# masterboard_b12.net
KiCad netlist of a schematic drawn in EAGLE
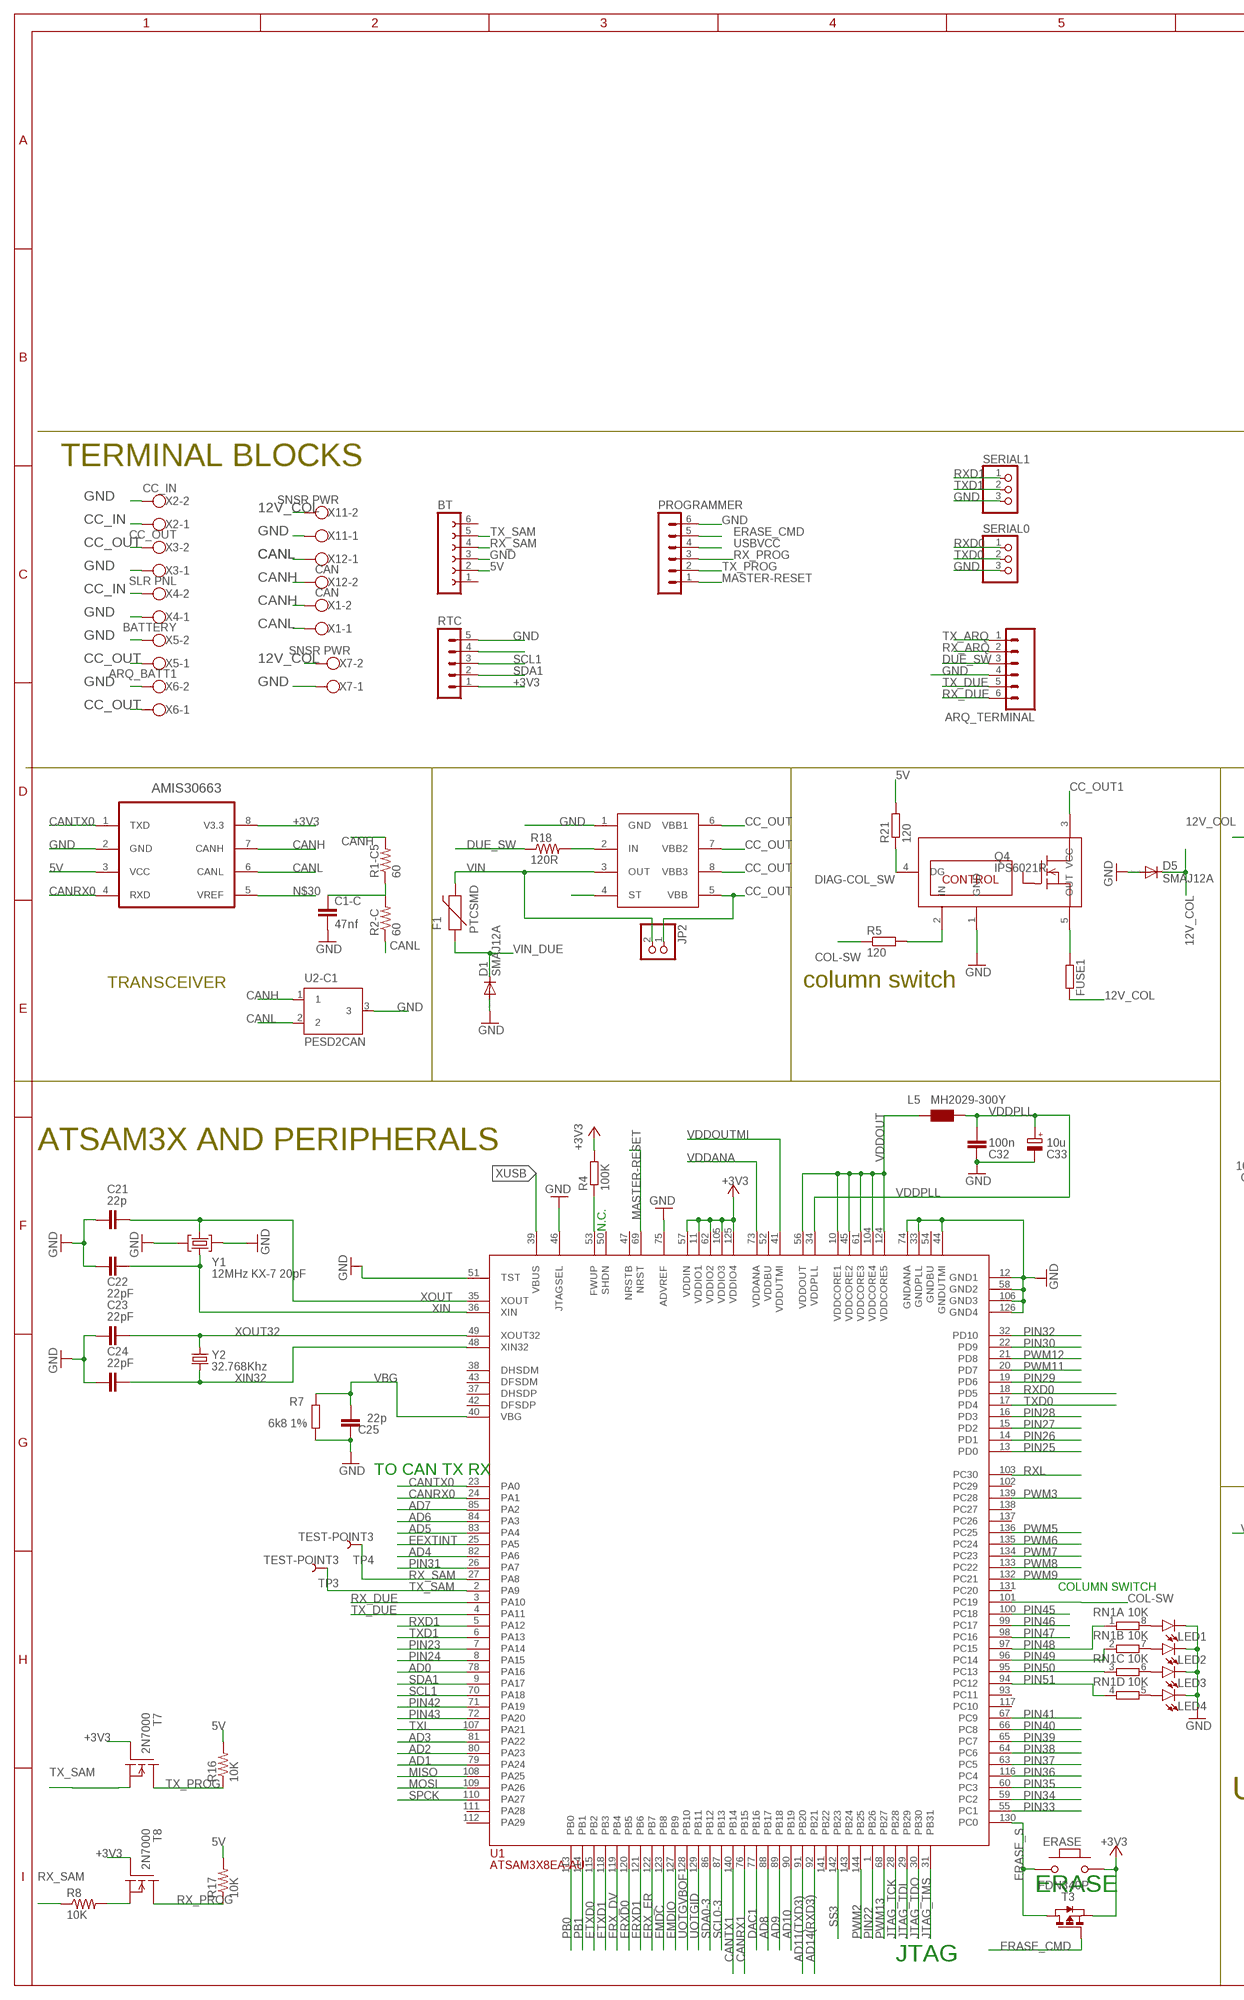
[diagram p0: schematic, sheet 1, part 1 of 2]
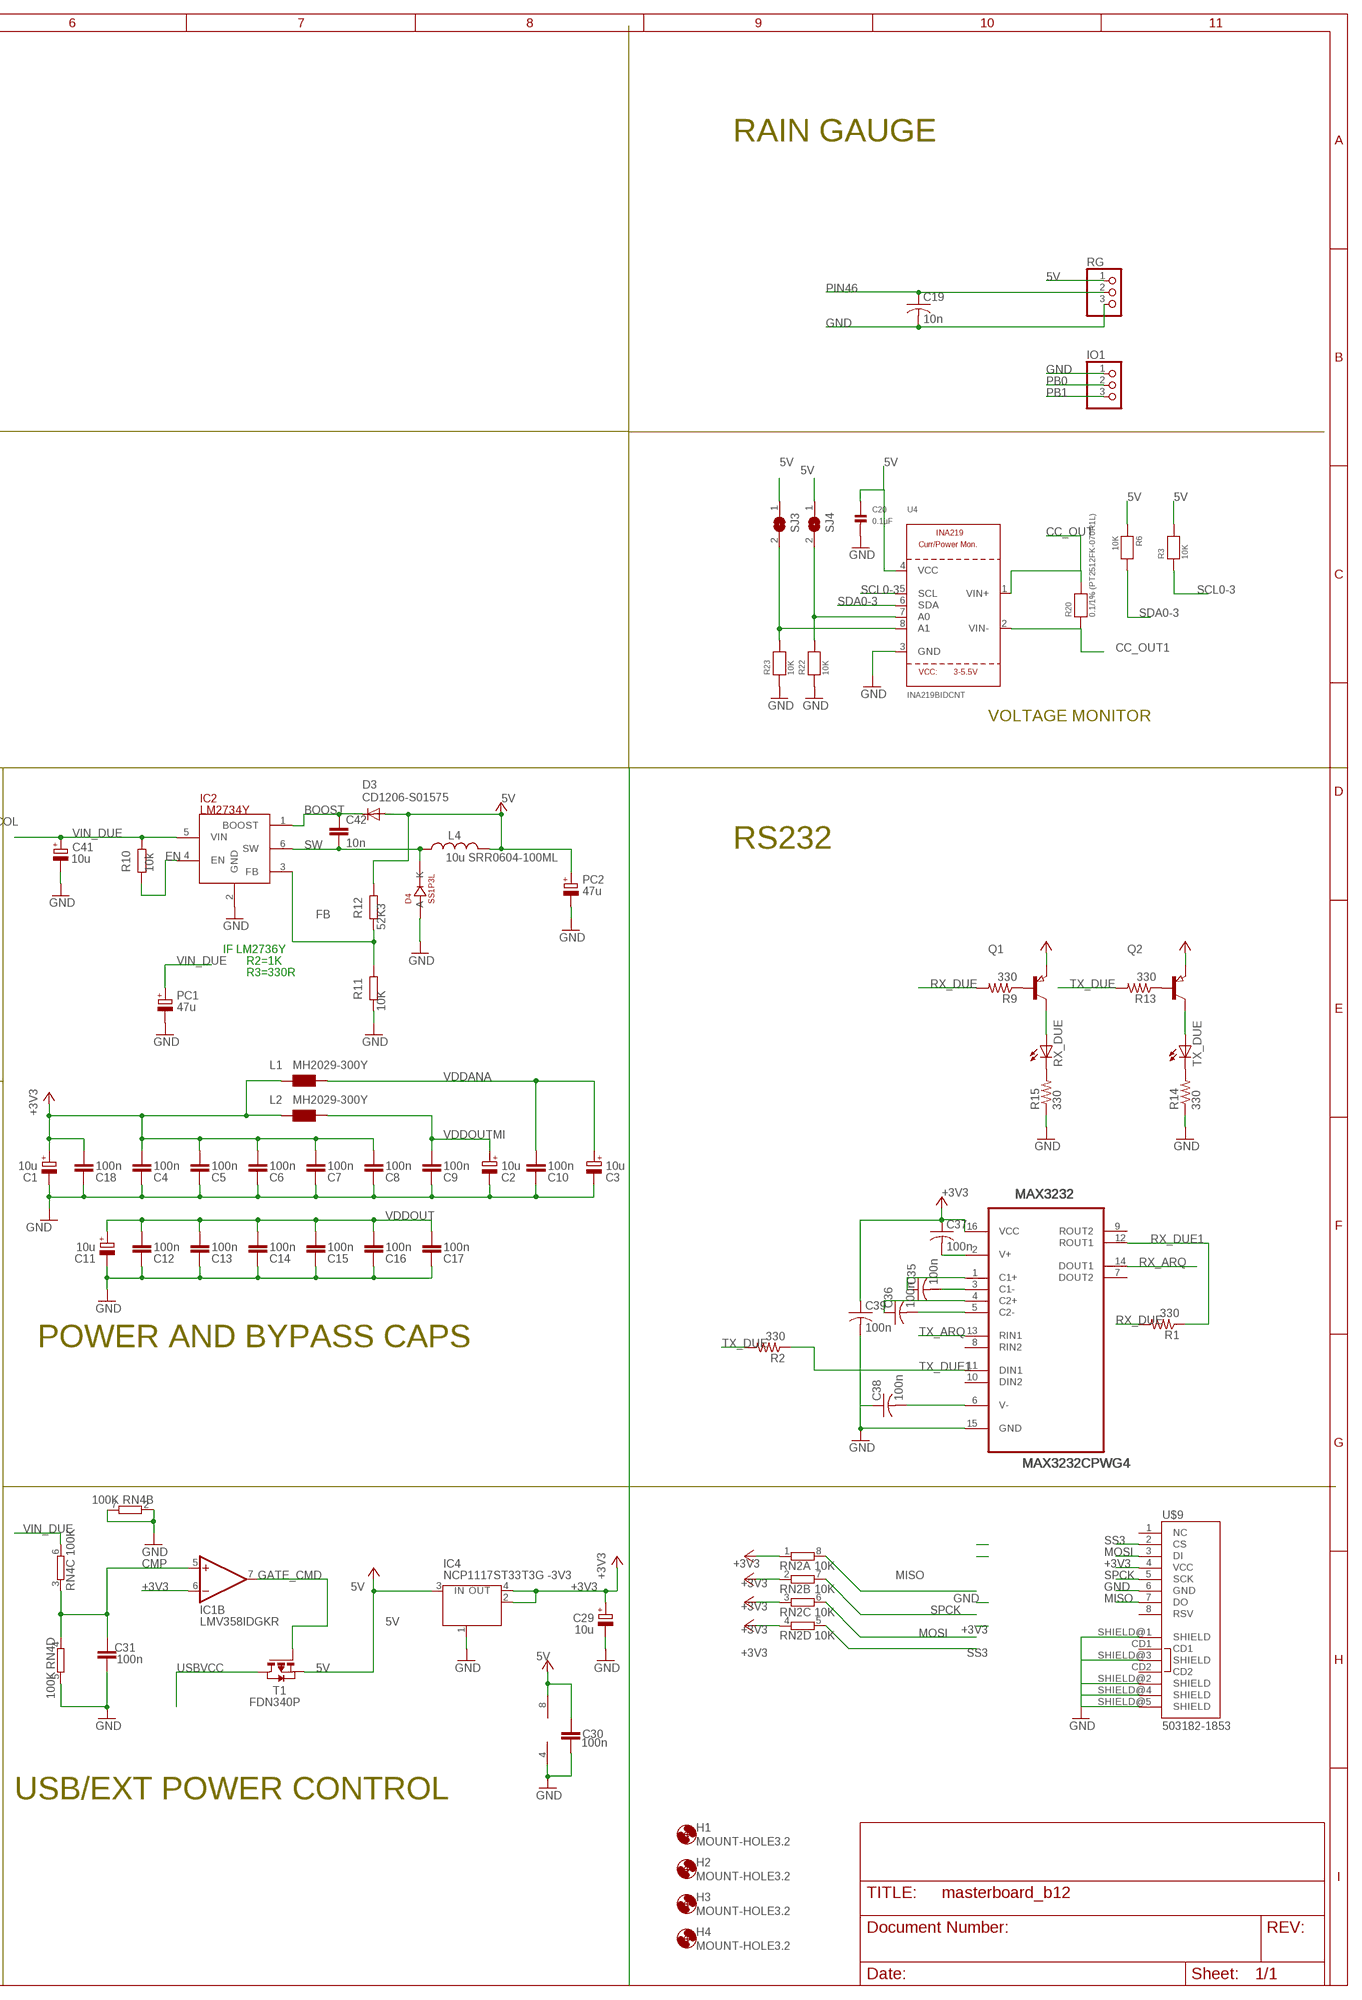
[diagram p1: schematic, sheet 1, part 2 of 2]

(export (version "E")
  (design (tool "Eeschema 10.0.6"))
  (components
    (comp (ref "ARQ_TERMINAL")
      (value "M06POLAR")
      (footprint "eagle-import:MOLEX-1X6")
      (libsource (lib "eagle-import") (part "M06POLAR"))
    )
    (comp (ref "BT")
      (value "FE06-1")
      (footprint "eagle-import:FE06")
      (libsource (lib "eagle-import") (part "FE06-1"))
    )
    (comp (ref "C1")
      (value "10u")
      (footprint "eagle-import:SMC_B")
      (libsource (lib "eagle-import") (part "CPOL-EUSMCB"))
    )
    (comp (ref "C1-C")
      (value "47nf")
      (footprint "eagle-import:C0805")
      (libsource (lib "eagle-import") (part "rcl_C-EUC0805"))
    )
    (comp (ref "C2")
      (value "10u")
      (footprint "eagle-import:SMC_B")
      (libsource (lib "eagle-import") (part "CPOL-EUSMCB"))
    )
    (comp (ref "C3")
      (value "10u")
      (footprint "eagle-import:SMC_B")
      (libsource (lib "eagle-import") (part "CPOL-EUSMCB"))
    )
    (comp (ref "C4")
      (value "100n")
      (footprint "eagle-import:C0402")
      (libsource (lib "eagle-import") (part "C-EUC0402"))
    )
    (comp (ref "C5")
      (value "100n")
      (footprint "eagle-import:C0402")
      (libsource (lib "eagle-import") (part "C-EUC0402"))
    )
    (comp (ref "C6")
      (value "100n")
      (footprint "eagle-import:C0402")
      (libsource (lib "eagle-import") (part "C-EUC0402"))
    )
    (comp (ref "C7")
      (value "100n")
      (footprint "eagle-import:C0402")
      (libsource (lib "eagle-import") (part "C-EUC0402"))
    )
    (comp (ref "C8")
      (value "100n")
      (footprint "eagle-import:C0402")
      (libsource (lib "eagle-import") (part "C-EUC0402"))
    )
    (comp (ref "C9")
      (value "100n")
      (footprint "eagle-import:C0402")
      (libsource (lib "eagle-import") (part "C-EUC0402"))
    )
    (comp (ref "C10")
      (value "100n")
      (footprint "eagle-import:C0402")
      (libsource (lib "eagle-import") (part "C-EUC0402"))
    )
    (comp (ref "C11")
      (value "10u")
      (footprint "eagle-import:SMC_B")
      (libsource (lib "eagle-import") (part "CPOL-EUSMCB"))
    )
    (comp (ref "C12")
      (value "100n")
      (footprint "eagle-import:C0402")
      (libsource (lib "eagle-import") (part "C-EUC0402"))
    )
    (comp (ref "C13")
      (value "100n")
      (footprint "eagle-import:C0402")
      (libsource (lib "eagle-import") (part "C-EUC0402"))
    )
    (comp (ref "C14")
      (value "100n")
      (footprint "eagle-import:C0402")
      (libsource (lib "eagle-import") (part "C-EUC0402"))
    )
    (comp (ref "C15")
      (value "100n")
      (footprint "eagle-import:C0402")
      (libsource (lib "eagle-import") (part "C-EUC0402"))
    )
    (comp (ref "C16")
      (value "100n")
      (footprint "eagle-import:C0402")
      (libsource (lib "eagle-import") (part "C-EUC0402"))
    )
    (comp (ref "C17")
      (value "100n")
      (footprint "eagle-import:C0402")
      (libsource (lib "eagle-import") (part "C-EUC0402"))
    )
    (comp (ref "C18")
      (value "100n")
      (footprint "eagle-import:C0402")
      (libsource (lib "eagle-import") (part "C-EUC0402"))
    )
    (comp (ref "C19")
      (value "10n")
      (footprint "eagle-import:C0603")
      (libsource (lib "eagle-import") (part "C-USC0603"))
    )
    (comp (ref "C20")
      (value "0.1µF")
      (footprint "eagle-import:0603-MINI")
      (fields (field (name "MPN") "04023C104KAT2A"))
      (libsource (lib "eagle-import") (part "CAP_CERAMIC0603MINI"))
    )
    (comp (ref "C21")
      (value "22p")
      (footprint "eagle-import:C0402")
      (libsource (lib "eagle-import") (part "C-EUC0402"))
    )
    (comp (ref "C22")
      (value "22pF")
      (footprint "eagle-import:C0402")
      (libsource (lib "eagle-import") (part "C-EUC0402"))
    )
    (comp (ref "C23")
      (value "22pF")
      (footprint "eagle-import:C0402")
      (libsource (lib "eagle-import") (part "C-EUC0402"))
    )
    (comp (ref "C24")
      (value "22pF")
      (footprint "eagle-import:C0402")
      (libsource (lib "eagle-import") (part "C-EUC0402"))
    )
    (comp (ref "C25")
      (value "22p")
      (footprint "eagle-import:C0402")
      (libsource (lib "eagle-import") (part "C-EUC0402"))
    )
    (comp (ref "C29")
      (value "10u")
      (footprint "eagle-import:SMC_B")
      (libsource (lib "eagle-import") (part "CPOL-EUSMCB"))
    )
    (comp (ref "C30")
      (value "100n")
      (footprint "eagle-import:C0402")
      (libsource (lib "eagle-import") (part "C-EUC0402"))
    )
    (comp (ref "C31")
      (value "100n")
      (footprint "eagle-import:C0402")
      (libsource (lib "eagle-import") (part "C-EUC0402"))
    )
    (comp (ref "C32")
      (value "100n")
      (footprint "eagle-import:C0402")
      (libsource (lib "eagle-import") (part "C-EUC0402"))
    )
    (comp (ref "C33")
      (value "10u")
      (footprint "eagle-import:SMC_B")
      (libsource (lib "eagle-import") (part "CPOL-EUSMCB"))
    )
    (comp (ref "C35")
      (value "100n")
      (footprint "eagle-import:C0603")
      (libsource (lib "eagle-import") (part "C-USC0603"))
    )
    (comp (ref "C36")
      (value "100n")
      (footprint "eagle-import:C0603")
      (libsource (lib "eagle-import") (part "C-USC0603"))
    )
    (comp (ref "C37")
      (value "100n")
      (footprint "eagle-import:C0603")
      (libsource (lib "eagle-import") (part "C-USC0603"))
    )
    (comp (ref "C38")
      (value "100n")
      (footprint "eagle-import:C0603")
      (libsource (lib "eagle-import") (part "C-USC0603"))
    )
    (comp (ref "C39")
      (value "100n")
      (footprint "eagle-import:C0603")
      (libsource (lib "eagle-import") (part "C-USC0603"))
    )
    (comp (ref "C41")
      (value "10u")
      (footprint "eagle-import:SMC_B")
      (libsource (lib "eagle-import") (part "CPOL-EUSMCB"))
    )
    (comp (ref "C42")
      (value "10n")
      (footprint "eagle-import:C0603-ROUND")
      (libsource (lib "eagle-import") (part "C-EUC0603"))
    )
    (comp (ref "D1")
      (value "SMAJ12A")
      (footprint "eagle-import:DO214AC")
      (libsource (lib "eagle-import") (part "DIODE-DO214AC"))
    )
    (comp (ref "D3")
      (value "CD1206-S01575")
      (footprint "eagle-import:MINIMELF")
      (libsource (lib "eagle-import") (part "DIODE-MINIMELF"))
    )
    (comp (ref "D4")
      (value "SS1P3L")
      (footprint "eagle-import:DO220AAL")
      (libsource (lib "eagle-import") (part "SS1P3L"))
    )
    (comp (ref "D5")
      (value "SMAJ12A")
      (footprint "eagle-import:DO214AC")
      (libsource (lib "eagle-import") (part "DIODE-DO214AC"))
    )
    (comp (ref "ERASE")
      (value "MYSMD_PB157")
      (footprint "eagle-import:SMD_157SW")
      (libsource (lib "eagle-import") (part "MYSMD_PB157"))
    )
    (comp (ref "F1")
      (value "PTCSMD")
      (footprint "eagle-import:PTC-1206")
      (libsource (lib "eagle-import") (part "PTCSMD"))
    )
    (comp (ref "FUSE1")
      (value "R-EU_1812X7R")
      (footprint "eagle-import:1812X7R")
      (libsource (lib "eagle-import") (part "R-EU_1812X7R"))
    )
    (comp (ref "H1")
      (value "MOUNT-HOLE3.2")
      (footprint "eagle-import:3,2")
      (libsource (lib "eagle-import") (part "MOUNT-HOLE3.2"))
    )
    (comp (ref "H2")
      (value "MOUNT-HOLE3.2")
      (footprint "eagle-import:3,2")
      (libsource (lib "eagle-import") (part "MOUNT-HOLE3.2"))
    )
    (comp (ref "H3")
      (value "MOUNT-HOLE3.2")
      (footprint "eagle-import:3,2")
      (libsource (lib "eagle-import") (part "MOUNT-HOLE3.2"))
    )
    (comp (ref "H4")
      (value "MOUNT-HOLE3.2")
      (footprint "eagle-import:3,2")
      (libsource (lib "eagle-import") (part "MOUNT-HOLE3.2"))
    )
    (comp (ref "IC1")
      (value "LMV358IDGKR")
      (footprint "eagle-import:MSOP08")
      (libsource (lib "eagle-import") (part "LMV358?MMX"))
    )
    (comp (ref "IC2")
      (value "LM2734Y")
      (footprint "eagle-import:SOT23-6")
      (libsource (lib "eagle-import") (part "LM2736Y"))
    )
    (comp (ref "IC4")
      (value "NCP1117ST33T3G -3V3")
      (footprint "eagle-import:SOT223")
      (libsource (lib "eagle-import") (part "MC33269ST-3.3T3"))
    )
    (comp (ref "IO1")
      (value "PINHD-1X3")
      (footprint "eagle-import:1X03")
      (libsource (lib "eagle-import") (part "PINHD-1X3"))
    )
    (comp (ref "JP2")
      (value "PINHD-1X2")
      (footprint "eagle-import:1X02")
      (libsource (lib "eagle-import") (part "PINHD-1X2"))
    )
    (comp (ref "L1")
      (value "MH2029-300Y")
      (footprint "eagle-import:0805")
      (libsource (lib "eagle-import") (part "WE-CBF_0805"))
    )
    (comp (ref "L2")
      (value "MH2029-300Y")
      (footprint "eagle-import:0805")
      (libsource (lib "eagle-import") (part "WE-CBF_0805"))
    )
    (comp (ref "L4")
      (value "10u SRR0604-100ML")
      (footprint "eagle-import:SRR0604")
      (libsource (lib "eagle-import") (part "L-USSRR0604"))
    )
    (comp (ref "L5")
      (value "MH2029-300Y")
      (footprint "eagle-import:0805")
      (libsource (lib "eagle-import") (part "WE-CBF_0805"))
    )
    (comp (ref "LED1")
      (value "LED0603")
      (footprint "eagle-import:LED-0603")
      (libsource (lib "eagle-import") (part "LED0603"))
    )
    (comp (ref "LED2")
      (value "LED0603")
      (footprint "eagle-import:LED-0603")
      (libsource (lib "eagle-import") (part "LED0603"))
    )
    (comp (ref "LED3")
      (value "LED0603")
      (footprint "eagle-import:LED-0603")
      (libsource (lib "eagle-import") (part "LED0603"))
    )
    (comp (ref "LED4")
      (value "LED0603")
      (footprint "eagle-import:LED-0603")
      (libsource (lib "eagle-import") (part "LED0603"))
    )
    (comp (ref "MAX3232")
      (value "MAX3232CPWG4")
      (footprint "eagle-import:SOP65P640X120-16N")
      (libsource (lib "eagle-import") (part "MAX3232CPWG4"))
    )
    (comp (ref "PC1")
      (value "47u")
      (footprint "eagle-import:PANASONIC_D")
      (libsource (lib "eagle-import") (part "CPOL-EUD"))
    )
    (comp (ref "PC2")
      (value "47u")
      (footprint "eagle-import:PANASONIC_D")
      (libsource (lib "eagle-import") (part "CPOL-EUD"))
    )
    (comp (ref "PROGRAMMER")
      (value "MA06-1")
      (footprint "eagle-import:MA06-1")
      (libsource (lib "eagle-import") (part "MA06-1"))
    )
    (comp (ref "Q1")
      (value "PNP-TRANSISTOR_SOT23")
      (footprint "eagle-import:SOT23")
      (libsource (lib "eagle-import") (part "PNP-TRANSISTOR_SOT23"))
    )
    (comp (ref "Q2")
      (value "PNP-TRANSISTOR_SOT23")
      (footprint "eagle-import:SOT23")
      (libsource (lib "eagle-import") (part "PNP-TRANSISTOR_SOT23"))
    )
    (comp (ref "Q4")
      (value "IPS6021R")
      (footprint "eagle-import:DPAK-5LEAD")
      (libsource (lib "eagle-import") (part "IPS6021R"))
    )
    (comp (ref "R1")
      (value "330")
      (footprint "eagle-import:R0603")
      (libsource (lib "eagle-import") (part "R-US_R0603"))
    )
    (comp (ref "R1-C5")
      (value "60")
      (footprint "eagle-import:R2512")
      (libsource (lib "eagle-import") (part "rcl_R-US_R2512"))
    )
    (comp (ref "R2")
      (value "330")
      (footprint "eagle-import:R0603")
      (libsource (lib "eagle-import") (part "R-US_R0603"))
    )
    (comp (ref "R2-C")
      (value "60")
      (footprint "eagle-import:R2512")
      (libsource (lib "eagle-import") (part "rcl_R-US_R2512"))
    )
    (comp (ref "R3")
      (value "10K")
      (footprint "eagle-import:0603-MINI")
      (fields (field (name "MPN") "TNPW040210K0BEED"))
      (libsource (lib "eagle-import") (part "RESISTOR0603MINI"))
    )
    (comp (ref "R4")
      (value "100K")
      (footprint "eagle-import:R0402")
      (libsource (lib "eagle-import") (part "R-EU_R0402"))
    )
    (comp (ref "R5")
      (value "120")
      (footprint "eagle-import:R0603")
      (libsource (lib "eagle-import") (part "rcl_R-EU_R0603"))
    )
    (comp (ref "R6")
      (value "10K")
      (footprint "eagle-import:0603-MINI")
      (fields (field (name "MPN") "TNPW040210K0BEED"))
      (libsource (lib "eagle-import") (part "RESISTOR0603MINI"))
    )
    (comp (ref "R7")
      (value "6k8 1%")
      (footprint "eagle-import:R0603-ROUND")
      (libsource (lib "eagle-import") (part "R-EU_R0603"))
    )
    (comp (ref "R8")
      (value "10K")
      (footprint "eagle-import:R0603")
      (libsource (lib "eagle-import") (part "rcl_R-US_R0603"))
    )
    (comp (ref "R9")
      (value "330")
      (footprint "eagle-import:R0603")
      (libsource (lib "eagle-import") (part "R-US_R0603"))
    )
    (comp (ref "R10")
      (value "10k")
      (footprint "eagle-import:R0402")
      (libsource (lib "eagle-import") (part "R-EU_R0402"))
    )
    (comp (ref "R11")
      (value "10K")
      (footprint "eagle-import:R0603-ROUND")
      (libsource (lib "eagle-import") (part "R-EU_0603-RND"))
    )
    (comp (ref "R12")
      (value "52K3")
      (footprint "eagle-import:R0603-ROUND")
      (libsource (lib "eagle-import") (part "R-EU_0603-RND"))
    )
    (comp (ref "R13")
      (value "330")
      (footprint "eagle-import:R0603")
      (libsource (lib "eagle-import") (part "R-US_R0603"))
    )
    (comp (ref "R14")
      (value "330")
      (footprint "eagle-import:R0603")
      (libsource (lib "eagle-import") (part "R-US_R0603"))
    )
    (comp (ref "R15")
      (value "330")
      (footprint "eagle-import:R0603")
      (libsource (lib "eagle-import") (part "R-US_R0603"))
    )
    (comp (ref "R16")
      (value "10K")
      (footprint "eagle-import:R0603")
      (libsource (lib "eagle-import") (part "rcl_R-US_R0603"))
    )
    (comp (ref "R17")
      (value "10K")
      (footprint "eagle-import:R0603")
      (libsource (lib "eagle-import") (part "rcl_R-US_R0603"))
    )
    (comp (ref "R18")
      (value "120R")
      (footprint "eagle-import:R0603")
      (libsource (lib "eagle-import") (part "rcl_R-US_R0603"))
    )
    (comp (ref "R20")
      (value "0.1/1% (PT2512FK-070R1L)")
      (footprint "eagle-import:2512")
      (libsource (lib "eagle-import") (part "RESISTOR2512"))
    )
    (comp (ref "R21")
      (value "120")
      (footprint "eagle-import:R0603")
      (libsource (lib "eagle-import") (part "rcl_R-EU_R0603"))
    )
    (comp (ref "R22")
      (value "10K")
      (footprint "eagle-import:0603-MINI")
      (fields (field (name "MPN") "TNPW040210K0BEED"))
      (libsource (lib "eagle-import") (part "RESISTOR0603MINI"))
    )
    (comp (ref "R23")
      (value "10K")
      (footprint "eagle-import:0603-MINI")
      (fields (field (name "MPN") "TNPW040210K0BEED"))
      (libsource (lib "eagle-import") (part "RESISTOR0603MINI"))
    )
    (comp (ref "RG")
      (value "PINHD-1X3")
      (footprint "eagle-import:1X03")
      (libsource (lib "eagle-import") (part "PINHD-1X3"))
    )
    (comp (ref "RN1")
      (value "10K")
      (footprint "eagle-import:CAT16")
      (libsource (lib "eagle-import") (part "4R-NCAT16"))
    )
    (comp (ref "RN2")
      (value "10K")
      (footprint "eagle-import:CAT16")
      (libsource (lib "eagle-import") (part "4R-NCAT16"))
    )
    (comp (ref "RN4")
      (value "100K")
      (footprint "eagle-import:CAT16")
      (libsource (lib "eagle-import") (part "4R-NCAT16"))
    )
    (comp (ref "RTC")
      (value "MA05-1")
      (footprint "eagle-import:MA05-1")
      (libsource (lib "eagle-import") (part "MA05-1"))
    )
    (comp (ref "RX_DUE")
      (value "LEDCHIPLED_0603")
      (footprint "eagle-import:CHIPLED_0603")
      (libsource (lib "eagle-import") (part "LEDCHIPLED_0603"))
    )
    (comp (ref "SERIAL0")
      (value "PINHD-1X3")
      (footprint "eagle-import:1X03")
      (libsource (lib "eagle-import") (part "PINHD-1X3"))
    )
    (comp (ref "SERIAL1")
      (value "PINHD-1X3")
      (footprint "eagle-import:1X03")
      (libsource (lib "eagle-import") (part "PINHD-1X3"))
    )
    (comp (ref "SJ3")
      (value "SOLDERJUMPERREFLOW_NOPASTE")
      (footprint "eagle-import:SOLDERJUMPER_REFLOW_NOPASTE")
      (libsource (lib "eagle-import") (part "SOLDERJUMPERREFLOW_NOPASTE"))
    )
    (comp (ref "SJ4")
      (value "SOLDERJUMPERREFLOW_NOPASTE")
      (footprint "eagle-import:SOLDERJUMPER_REFLOW_NOPASTE")
      (libsource (lib "eagle-import") (part "SOLDERJUMPERREFLOW_NOPASTE"))
    )
    (comp (ref "T1")
      (value "FDN340P")
      (footprint "eagle-import:SOT-23")
      (libsource (lib "eagle-import") (part "PMOSSOT23"))
    )
    (comp (ref "T3")
      (value "FDN340P")
      (footprint "eagle-import:SOT-23")
      (libsource (lib "eagle-import") (part "PMOSSOT23"))
    )
    (comp (ref "T7")
      (value "2N7000")
      (footprint "eagle-import:SOT23")
      (libsource (lib "eagle-import") (part "2N7000"))
    )
    (comp (ref "T8")
      (value "2N7000")
      (footprint "eagle-import:SOT23")
      (libsource (lib "eagle-import") (part "2N7000"))
    )
    (comp (ref "TP3")
      (value "TEST-POINT3")
      (footprint "eagle-import:PAD.03X.03")
      (libsource (lib "eagle-import") (part "TEST-POINT3"))
    )
    (comp (ref "TP4")
      (value "TEST-POINT3")
      (footprint "eagle-import:PAD.03X.03")
      (libsource (lib "eagle-import") (part "TEST-POINT3"))
    )
    (comp (ref "TX_DUE")
      (value "LEDCHIPLED_0603")
      (footprint "eagle-import:CHIPLED_0603")
      (libsource (lib "eagle-import") (part "LEDCHIPLED_0603"))
    )
    (comp (ref "U$9")
      (value "503182-1853")
      (footprint "eagle-import:503182-1853")
      (libsource (lib "eagle-import") (part "503182-1853"))
    )
    (comp (ref "U1")
      (value "ATSAM3X8EA-AU")
      (footprint "eagle-import:LQFP144")
      (libsource (lib "eagle-import") (part "ATSAM3X/AAU"))
    )
    (comp (ref "U2")
      (value "INF-PG-DSO-8-24_L_1")
      (footprint "eagle-import:INF-PG-DSO-8-24_L_1PRIMARY")
      (libsource (lib "eagle-import") (part "INF-PG-DSO-8-24_L_1"))
    )
    (comp (ref "U2-C")
      (value "AMIS30663CAN")
      (footprint "eagle-import:SOIC8")
      (fields (field (name "MPN") "AMIS30663"))
      (libsource (lib "eagle-import") (part "AMIS30663CAN"))
    )
    (comp (ref "U2-C1")
      (value "PESD2CAN")
      (footprint "eagle-import:SOT23")
      (libsource (lib "eagle-import") (part "PESD2CAN"))
    )
    (comp (ref "U4")
      (value "INA219BIDCNT")
      (footprint "eagle-import:SOT23-8")
      (libsource (lib "eagle-import") (part "INA219"))
    )
    (comp (ref "X1")
      (value "CAN")
      (footprint "eagle-import:W237-102")
      (fields (field (name "MPN") "237-102"))
      (libsource (lib "eagle-import") (part "W237-102"))
    )
    (comp (ref "X2")
      (value "CC_IN")
      (footprint "eagle-import:W237-102")
      (fields (field (name "MPN") "237-102"))
      (libsource (lib "eagle-import") (part "W237-102"))
    )
    (comp (ref "X3")
      (value "CC_OUT")
      (footprint "eagle-import:W237-102")
      (fields (field (name "MPN") "237-102"))
      (libsource (lib "eagle-import") (part "W237-102"))
    )
    (comp (ref "X4")
      (value "SLR PNL")
      (footprint "eagle-import:W237-102")
      (fields (field (name "MPN") "237-102"))
      (libsource (lib "eagle-import") (part "W237-102"))
    )
    (comp (ref "X5")
      (value "BATTERY")
      (footprint "eagle-import:W237-102")
      (fields (field (name "MPN") "237-102"))
      (libsource (lib "eagle-import") (part "W237-102"))
    )
    (comp (ref "X6")
      (value "ARQ_BATT1")
      (footprint "eagle-import:W237-102")
      (fields (field (name "MPN") "237-102"))
      (libsource (lib "eagle-import") (part "W237-102"))
    )
    (comp (ref "X7")
      (value "SNSR PWR")
      (footprint "eagle-import:W237-102")
      (fields (field (name "MPN") "237-102"))
      (libsource (lib "eagle-import") (part "W237-102"))
    )
    (comp (ref "X11")
      (value "SNSR PWR")
      (footprint "eagle-import:W237-102")
      (fields (field (name "MPN") "237-102"))
      (libsource (lib "eagle-import") (part "W237-102"))
    )
    (comp (ref "X12")
      (value "CAN")
      (footprint "eagle-import:W237-102")
      (fields (field (name "MPN") "237-102"))
      (libsource (lib "eagle-import") (part "W237-102"))
    )
    (comp (ref "Y1")
      (value "12MHz KX-7 20pF")
      (footprint "eagle-import:CRYSTAL-3.2-2.5")
      (libsource (lib "eagle-import") (part "CRYSTAL-3.2-2.5"))
    )
    (comp (ref "Y2")
      (value "32.768Khz")
      (footprint "eagle-import:RESONATOR_EPSON_FC_145")
      (libsource (lib "eagle-import") (part "RESONATOR_EPSON_FC_145"))
    )
  )
  (nets
    (net (code "1") (name "+3V3") (class "Default")
      (node (ref "C1") (pin "+") (pinfunction "+_+") (pintype "passive"))
      (node (ref "C18") (pin "2") (pinfunction "2_2") (pintype "passive"))
      (node (ref "C29") (pin "+") (pinfunction "+_+") (pintype "passive"))
      (node (ref "C37") (pin "1") (pinfunction "1_1") (pintype "passive"))
      (node (ref "C39") (pin "1") (pinfunction "1_1") (pintype "passive"))
      (node (ref "C4") (pin "2") (pinfunction "2_2") (pintype "passive"))
      (node (ref "C5") (pin "2") (pinfunction "2_2") (pintype "passive"))
      (node (ref "C6") (pin "2") (pinfunction "2_2") (pintype "passive"))
      (node (ref "C7") (pin "2") (pinfunction "2_2") (pintype "passive"))
      (node (ref "C8") (pin "2") (pinfunction "2_2") (pintype "passive"))
      (node (ref "ERASE") (pin "1") (pinfunction "1_1") (pintype "passive"))
      (node (ref "IC1") (pin "6") (pinfunction "-IN_6") (pintype "input"))
      (node (ref "IC4") (pin "2") (pinfunction "OUT_2") (pintype "passive"))
      (node (ref "IC4") (pin "4") (pinfunction "OUT_4") (pintype "passive"))
      (node (ref "L1") (pin "1") (pinfunction "1_1") (pintype "passive"))
      (node (ref "L2") (pin "1") (pinfunction "1_1") (pintype "passive"))
      (node (ref "MAX3232") (pin "16") (pinfunction "VCC_16") (pintype "power_in"))
      (node (ref "Q1") (pin "2") (pinfunction "E_2") (pintype "passive"))
      (node (ref "Q2") (pin "2") (pinfunction "E_2") (pintype "passive"))
      (node (ref "R4") (pin "2") (pinfunction "2_2") (pintype "passive"))
      (node (ref "RN2") (pin "1") (pinfunction "1_1") (pintype "passive"))
      (node (ref "RN2") (pin "2") (pinfunction "1_2") (pintype "passive"))
      (node (ref "RN2") (pin "3") (pinfunction "1_3") (pintype "passive"))
      (node (ref "RN2") (pin "4") (pinfunction "1_4") (pintype "passive"))
      (node (ref "RTC") (pin "1") (pinfunction "1_1") (pintype "passive"))
      (node (ref "T3") (pin "2") (pinfunction "S_2") (pintype "passive"))
      (node (ref "T7") (pin "1") (pinfunction "G_1") (pintype "passive"))
      (node (ref "T8") (pin "1") (pinfunction "G_1") (pintype "passive"))
      (node (ref "U$9") (pin "4") (pinfunction "VCC_4") (pintype "bidirectional"))
      (node (ref "U1") (pin "105") (pinfunction "VDDIO3_105") (pintype "power_in"))
      (node (ref "U1") (pin "11") (pinfunction "VDDIO1_11") (pintype "power_in"))
      (node (ref "U1") (pin "125") (pinfunction "VDDIO4_125") (pintype "power_in"))
      (node (ref "U1") (pin "57") (pinfunction "VDDIN_57") (pintype "power_in"))
      (node (ref "U1") (pin "62") (pinfunction "VDDIO2_62") (pintype "power_in"))
      (node (ref "U2-C") (pin "8") (pinfunction "V3.3_8") (pintype "bidirectional"))
    )
    (net (code "2") (name "+5V") (class "Default")
      (node (ref "BT") (pin "2") (pinfunction "2_2") (pintype "passive"))
      (node (ref "C20") (pin "1") (pinfunction "P$1_1") (pintype "passive"))
      (node (ref "C30") (pin "2") (pinfunction "2_2") (pintype "passive"))
      (node (ref "D3") (pin "A") (pinfunction "A_A") (pintype "passive"))
      (node (ref "IC1") (pin "8") (pinfunction "V+_8") (pintype "power_in"))
      (node (ref "IC4") (pin "3") (pinfunction "IN_3") (pintype "input"))
      (node (ref "L4") (pin "P$2") (pinfunction "2_P$2") (pintype "passive"))
      (node (ref "PC2") (pin "+") (pinfunction "+_+") (pintype "passive"))
      (node (ref "R12") (pin "1") (pinfunction "1_1") (pintype "passive"))
      (node (ref "R16") (pin "2") (pinfunction "2_2") (pintype "passive"))
      (node (ref "R17") (pin "2") (pinfunction "2_2") (pintype "passive"))
      (node (ref "R21") (pin "2") (pinfunction "2_2") (pintype "passive"))
      (node (ref "R3") (pin "2") (pinfunction "2_2") (pintype "passive"))
      (node (ref "R6") (pin "1") (pinfunction "1_1") (pintype "passive"))
      (node (ref "RG") (pin "1") (pinfunction "1_1") (pintype "passive"))
      (node (ref "SJ3") (pin "1") (pinfunction "1_1") (pintype "passive"))
      (node (ref "SJ4") (pin "1") (pinfunction "1_1") (pintype "passive"))
      (node (ref "T1") (pin "2") (pinfunction "S_2") (pintype "passive"))
      (node (ref "U2-C") (pin "3") (pinfunction "VCC_3") (pintype "bidirectional"))
      (node (ref "U4") (pin "4") (pinfunction "VCC_4") (pintype "bidirectional"))
    )
    (net (code "3") (name "/12V_COL") (class "Default")
      (node (ref "D5") (pin "C") (pinfunction "C_C") (pintype "passive"))
      (node (ref "FUSE1") (pin "2") (pinfunction "2_2") (pintype "passive"))
      (node (ref "X11") (pin "2") (pinfunction "KL_2") (pintype "passive"))
      (node (ref "X7") (pin "2") (pinfunction "KL_2") (pintype "passive"))
    )
    (net (code "4") (name "/AD0") (class "Default")
      (node (ref "U1") (pin "78") (pinfunction "PA16_78") (pintype "bidirectional"))
    )
    (net (code "5") (name "/AD1") (class "Default")
      (node (ref "U1") (pin "79") (pinfunction "PA24_79") (pintype "bidirectional"))
    )
    (net (code "6") (name "/AD2") (class "Default")
      (node (ref "U1") (pin "80") (pinfunction "PA23_80") (pintype "bidirectional"))
    )
    (net (code "7") (name "/AD3") (class "Default")
      (node (ref "U1") (pin "81") (pinfunction "PA22_81") (pintype "bidirectional"))
    )
    (net (code "8") (name "/AD4") (class "Default")
      (node (ref "U1") (pin "82") (pinfunction "PA6_82") (pintype "bidirectional"))
    )
    (net (code "9") (name "/AD5") (class "Default")
      (node (ref "U1") (pin "83") (pinfunction "PA4_83") (pintype "bidirectional"))
    )
    (net (code "10") (name "/AD6") (class "Default")
      (node (ref "U1") (pin "84") (pinfunction "PA3_84") (pintype "bidirectional"))
    )
    (net (code "11") (name "/AD7") (class "Default")
      (node (ref "U1") (pin "85") (pinfunction "PA2_85") (pintype "bidirectional"))
    )
    (net (code "12") (name "/AD8") (class "Default")
      (node (ref "U1") (pin "88") (pinfunction "PB17_88") (pintype "bidirectional"))
    )
    (net (code "13") (name "/AD9") (class "Default")
      (node (ref "U1") (pin "89") (pinfunction "PB18_89") (pintype "bidirectional"))
    )
    (net (code "14") (name "/AD10") (class "Default")
      (node (ref "U1") (pin "90") (pinfunction "PB19_90") (pintype "bidirectional"))
    )
    (net (code "15") (name "/AD11(TXD3)") (class "Default")
      (node (ref "U1") (pin "91") (pinfunction "PB20_91") (pintype "bidirectional"))
    )
    (net (code "16") (name "/AD14(RXD3)") (class "Default")
      (node (ref "U1") (pin "92") (pinfunction "PB21_92") (pintype "bidirectional"))
    )
    (net (code "17") (name "/BOOST") (class "Default")
      (node (ref "C42") (pin "1") (pinfunction "1_1") (pintype "passive"))
      (node (ref "D3") (pin "C") (pinfunction "C_C") (pintype "passive"))
      (node (ref "IC2") (pin "1") (pinfunction "BOOST_1") (pintype "input"))
    )
    (net (code "18") (name "/CANH") (class "Default")
      (node (ref "R1-C5") (pin "2") (pinfunction "2_2") (pintype "passive"))
      (node (ref "U2-C") (pin "7") (pinfunction "CANH_7") (pintype "bidirectional"))
      (node (ref "U2-C1") (pin "1") (pinfunction "1_1") (pintype "input"))
      (node (ref "X1") (pin "2") (pinfunction "KL_2") (pintype "passive"))
      (node (ref "X12") (pin "2") (pinfunction "KL_2") (pintype "passive"))
    )
    (net (code "19") (name "/CANL") (class "Default")
      (node (ref "R2-C") (pin "1") (pinfunction "1_1") (pintype "passive"))
      (node (ref "U2-C") (pin "6") (pinfunction "CANL_6") (pintype "bidirectional"))
      (node (ref "U2-C1") (pin "2") (pinfunction "2_2") (pintype "power_in"))
      (node (ref "X1") (pin "1") (pinfunction "KL_1") (pintype "passive"))
      (node (ref "X12") (pin "1") (pinfunction "KL_1") (pintype "passive"))
    )
    (net (code "20") (name "/CANRX0") (class "Default")
      (node (ref "U1") (pin "24") (pinfunction "PA1_24") (pintype "bidirectional"))
      (node (ref "U2-C") (pin "4") (pinfunction "RXD_4") (pintype "bidirectional"))
    )
    (net (code "21") (name "/CANRX1") (class "Default")
      (node (ref "U1") (pin "76") (pinfunction "PB15_76") (pintype "bidirectional"))
    )
    (net (code "22") (name "/CANTX0") (class "Default")
      (node (ref "U1") (pin "23") (pinfunction "PA0_23") (pintype "bidirectional"))
      (node (ref "U2-C") (pin "1") (pinfunction "TXD_1") (pintype "bidirectional"))
    )
    (net (code "23") (name "/CANTX1") (class "Default")
      (node (ref "U1") (pin "140") (pinfunction "PB14_140") (pintype "bidirectional"))
    )
    (net (code "24") (name "/CC_IN") (class "Default")
      (node (ref "X2") (pin "1") (pinfunction "KL_1") (pintype "passive"))
      (node (ref "X4") (pin "2") (pinfunction "KL_2") (pintype "passive"))
    )
    (net (code "25") (name "/CC_OUT") (class "Default")
      (node (ref "JP2") (pin "1") (pinfunction "1_1") (pintype "passive"))
      (node (ref "R20") (pin "2") (pinfunction "2_2") (pintype "passive"))
      (node (ref "U2") (pin "5") (pinfunction "VBB_5") (pintype "bidirectional"))
      (node (ref "U2") (pin "6") (pinfunction "VBB1_6") (pintype "bidirectional"))
      (node (ref "U2") (pin "7") (pinfunction "VBB2_7") (pintype "bidirectional"))
      (node (ref "U2") (pin "8") (pinfunction "VBB3_8") (pintype "bidirectional"))
      (node (ref "U4") (pin "1") (pinfunction "VIN+_1") (pintype "bidirectional"))
      (node (ref "X3") (pin "2") (pinfunction "KL_2") (pintype "passive"))
      (node (ref "X5") (pin "1") (pinfunction "KL_1") (pintype "passive"))
      (node (ref "X6") (pin "1") (pinfunction "KL_1") (pintype "passive"))
    )
    (net (code "26") (name "/CC_OUT1") (class "Default")
      (node (ref "Q4") (pin "3") (pinfunction "VCC_3") (pintype "passive"))
      (node (ref "R20") (pin "1") (pinfunction "1_1") (pintype "passive"))
      (node (ref "U4") (pin "2") (pinfunction "VIN-_2") (pintype "bidirectional"))
    )
    (net (code "27") (name "/CMP") (class "Default")
      (node (ref "C31") (pin "2") (pinfunction "2_2") (pintype "passive"))
      (node (ref "IC1") (pin "5") (pinfunction "+IN_5") (pintype "input"))
      (node (ref "RN4") (pin "3") (pinfunction "1_3") (pintype "passive"))
      (node (ref "RN4") (pin "4") (pinfunction "1_4") (pintype "passive"))
    )
    (net (code "28") (name "/COL-SW") (class "Default")
      (node (ref "R5") (pin "1") (pinfunction "1_1") (pintype "passive"))
      (node (ref "U1") (pin "101") (pinfunction "PC19_101") (pintype "bidirectional"))
    )
    (net (code "29") (name "/DAC1") (class "Default")
      (node (ref "U1") (pin "77") (pinfunction "PB16_77") (pintype "bidirectional"))
    )
    (net (code "30") (name "/DIAG-COL_SW") (class "Default")
      (node (ref "Q4") (pin "4") (pinfunction "DG_4") (pintype "passive"))
      (node (ref "R21") (pin "1") (pinfunction "1_1") (pintype "passive"))
    )
    (net (code "31") (name "/DUE_SW") (class "Default")
      (node (ref "ARQ_TERMINAL") (pin "3") (pinfunction "3_3") (pintype "passive"))
      (node (ref "R18") (pin "1") (pinfunction "1_1") (pintype "passive"))
    )
    (net (code "32") (name "/EEXTINT") (class "Default")
      (node (ref "U1") (pin "25") (pinfunction "PA5_25") (pintype "bidirectional"))
    )
    (net (code "33") (name "/EMDC") (class "Default")
      (node (ref "U1") (pin "123") (pinfunction "PB8_123") (pintype "bidirectional"))
    )
    (net (code "34") (name "/EMDIO") (class "Default")
      (node (ref "U1") (pin "127") (pinfunction "PB9_127") (pintype "bidirectional"))
    )
    (net (code "35") (name "/EN") (class "Default")
      (node (ref "IC2") (pin "4") (pinfunction "EN_4") (pintype "input"))
      (node (ref "R10") (pin "2") (pinfunction "2_2") (pintype "passive"))
    )
    (net (code "36") (name "/ERASE_CMD") (class "Default")
      (node (ref "PROGRAMMER") (pin "5") (pinfunction "5_5") (pintype "passive"))
      (node (ref "T3") (pin "3") (pinfunction "G_3") (pintype "passive"))
    )
    (net (code "37") (name "/ERASE_S") (class "Default")
      (node (ref "ERASE") (pin "2") (pinfunction "2_2") (pintype "passive"))
      (node (ref "T3") (pin "1") (pinfunction "D_1") (pintype "passive"))
      (node (ref "U1") (pin "130") (pinfunction "PC0_130") (pintype "bidirectional"))
    )
    (net (code "38") (name "/ERXD0") (class "Default")
      (node (ref "U1") (pin "120") (pinfunction "PB5_120") (pintype "bidirectional"))
    )
    (net (code "39") (name "/ERXD1") (class "Default")
      (node (ref "U1") (pin "121") (pinfunction "PB6_121") (pintype "bidirectional"))
    )
    (net (code "40") (name "/ERX_DV") (class "Default")
      (node (ref "U1") (pin "119") (pinfunction "PB4_119") (pintype "bidirectional"))
    )
    (net (code "41") (name "/ERX_ER") (class "Default")
      (node (ref "U1") (pin "122") (pinfunction "PB7_122") (pintype "bidirectional"))
    )
    (net (code "42") (name "/ETXD0") (class "Default")
      (node (ref "U1") (pin "115") (pinfunction "PB2_115") (pintype "bidirectional"))
    )
    (net (code "43") (name "/ETXD1") (class "Default")
      (node (ref "U1") (pin "118") (pinfunction "PB3_118") (pintype "bidirectional"))
    )
    (net (code "44") (name "/FB") (class "Default")
      (node (ref "IC2") (pin "3") (pinfunction "FB_3") (pintype "input"))
      (node (ref "R11") (pin "1") (pinfunction "1_1") (pintype "passive"))
      (node (ref "R12") (pin "2") (pinfunction "2_2") (pintype "passive"))
    )
    (net (code "45") (name "/GATE_CMD") (class "Default")
      (node (ref "IC1") (pin "7") (pinfunction "OUT_7") (pintype "output"))
      (node (ref "T1") (pin "3") (pinfunction "G_3") (pintype "passive"))
    )
    (net (code "46") (name "/GNDBU") (class "Default")
      (node (ref "U1") (pin "54") (pinfunction "GNDBU_54") (pintype "power_in"))
    )
    (net (code "47") (name "/JTAG_TCK") (class "Default")
      (node (ref "U1") (pin "28") (pinfunction "PB28_28") (pintype "bidirectional"))
    )
    (net (code "48") (name "/JTAG_TDI") (class "Default")
      (node (ref "U1") (pin "29") (pinfunction "PB29_29") (pintype "bidirectional"))
    )
    (net (code "49") (name "/JTAG_TDO") (class "Default")
      (node (ref "U1") (pin "30") (pinfunction "PB30_30") (pintype "bidirectional"))
    )
    (net (code "50") (name "/JTAG_TMS") (class "Default")
      (node (ref "U1") (pin "31") (pinfunction "PB31_31") (pintype "bidirectional"))
    )
    (net (code "51") (name "/MASTER-RESET") (class "Default")
      (node (ref "PROGRAMMER") (pin "1") (pinfunction "1_1") (pintype "passive"))
      (node (ref "U1") (pin "69") (pinfunction "NRST_69") (pintype "bidirectional"))
    )
    (net (code "52") (name "/MISO") (class "Default")
      (node (ref "RN2") (pin "8") (pinfunction "2_8") (pintype "passive"))
      (node (ref "U$9") (pin "7") (pinfunction "DO_7") (pintype "bidirectional"))
      (node (ref "U1") (pin "108") (pinfunction "PA25_108") (pintype "bidirectional"))
    )
    (net (code "53") (name "/MOSI") (class "Default")
      (node (ref "RN2") (pin "6") (pinfunction "2_6") (pintype "passive"))
      (node (ref "U$9") (pin "3") (pinfunction "DI_3") (pintype "bidirectional"))
      (node (ref "U1") (pin "109") (pinfunction "PA26_109") (pintype "bidirectional"))
    )
    (net (code "54") (name "/N$30") (class "Default")
      (node (ref "U2-C") (pin "5") (pinfunction "VREF_5") (pintype "bidirectional"))
    )
    (net (code "55") (name "/PB0") (class "Default")
      (node (ref "IO1") (pin "2") (pinfunction "2_2") (pintype "passive"))
      (node (ref "U1") (pin "113") (pinfunction "PB0_113") (pintype "bidirectional"))
    )
    (net (code "56") (name "/PB1") (class "Default")
      (node (ref "IO1") (pin "3") (pinfunction "3_3") (pintype "passive"))
      (node (ref "U1") (pin "114") (pinfunction "PB1_114") (pintype "bidirectional"))
    )
    (net (code "57") (name "/PIN22") (class "Default")
      (node (ref "U1") (pin "1") (pinfunction "PB26_1") (pintype "bidirectional"))
    )
    (net (code "58") (name "/PIN23") (class "Default")
      (node (ref "U1") (pin "7") (pinfunction "PA14_7") (pintype "bidirectional"))
    )
    (net (code "59") (name "/PIN24") (class "Default")
      (node (ref "U1") (pin "8") (pinfunction "PA15_8") (pintype "bidirectional"))
    )
    (net (code "60") (name "/PIN25") (class "Default")
      (node (ref "U1") (pin "13") (pinfunction "PD0_13") (pintype "bidirectional"))
    )
    (net (code "61") (name "/PIN26") (class "Default")
      (node (ref "U1") (pin "14") (pinfunction "PD1_14") (pintype "bidirectional"))
    )
    (net (code "62") (name "/PIN27") (class "Default")
      (node (ref "U1") (pin "15") (pinfunction "PD2_15") (pintype "bidirectional"))
    )
    (net (code "63") (name "/PIN28") (class "Default")
      (node (ref "U1") (pin "16") (pinfunction "PD3_16") (pintype "bidirectional"))
    )
    (net (code "64") (name "/PIN29") (class "Default")
      (node (ref "U1") (pin "19") (pinfunction "PD6_19") (pintype "bidirectional"))
    )
    (net (code "65") (name "/PIN30") (class "Default")
      (node (ref "U1") (pin "22") (pinfunction "PD9_22") (pintype "bidirectional"))
    )
    (net (code "66") (name "/PIN31") (class "Default")
      (node (ref "U1") (pin "26") (pinfunction "PA7_26") (pintype "bidirectional"))
    )
    (net (code "67") (name "/PIN32") (class "Default")
      (node (ref "U1") (pin "32") (pinfunction "PD10_32") (pintype "bidirectional"))
    )
    (net (code "68") (name "/PIN33") (class "Default")
      (node (ref "U1") (pin "55") (pinfunction "PC1_55") (pintype "bidirectional"))
    )
    (net (code "69") (name "/PIN34") (class "Default")
      (node (ref "U1") (pin "59") (pinfunction "PC2_59") (pintype "bidirectional"))
    )
    (net (code "70") (name "/PIN35") (class "Default")
      (node (ref "U1") (pin "60") (pinfunction "PC3_60") (pintype "bidirectional"))
    )
    (net (code "71") (name "/PIN36") (class "Default")
      (node (ref "U1") (pin "116") (pinfunction "PC4_116") (pintype "bidirectional"))
    )
    (net (code "72") (name "/PIN37") (class "Default")
      (node (ref "U1") (pin "63") (pinfunction "PC5_63") (pintype "bidirectional"))
    )
    (net (code "73") (name "/PIN38") (class "Default")
      (node (ref "U1") (pin "64") (pinfunction "PC6_64") (pintype "bidirectional"))
    )
    (net (code "74") (name "/PIN39") (class "Default")
      (node (ref "U1") (pin "65") (pinfunction "PC7_65") (pintype "bidirectional"))
    )
    (net (code "75") (name "/PIN40") (class "Default")
      (node (ref "U1") (pin "66") (pinfunction "PC8_66") (pintype "bidirectional"))
    )
    (net (code "76") (name "/PIN41") (class "Default")
      (node (ref "U1") (pin "67") (pinfunction "PC9_67") (pintype "bidirectional"))
    )
    (net (code "77") (name "/PIN42") (class "Default")
      (node (ref "U1") (pin "71") (pinfunction "PA19_71") (pintype "bidirectional"))
    )
    (net (code "78") (name "/PIN43") (class "Default")
      (node (ref "U1") (pin "72") (pinfunction "PA20_72") (pintype "bidirectional"))
    )
    (net (code "79") (name "/PIN45") (class "Default")
      (node (ref "U1") (pin "100") (pinfunction "PC18_100") (pintype "bidirectional"))
    )
    (net (code "80") (name "/PIN46") (class "Default")
      (node (ref "C19") (pin "1") (pinfunction "1_1") (pintype "passive"))
      (node (ref "RG") (pin "2") (pinfunction "2_2") (pintype "passive"))
      (node (ref "U1") (pin "99") (pinfunction "PC17_99") (pintype "bidirectional"))
    )
    (net (code "81") (name "/PIN47") (class "Default")
      (node (ref "U1") (pin "98") (pinfunction "PC16_98") (pintype "bidirectional"))
    )
    (net (code "82") (name "/PIN48") (class "Default")
      (node (ref "RN1") (pin "1") (pinfunction "1_1") (pintype "passive"))
      (node (ref "U1") (pin "97") (pinfunction "PC15_97") (pintype "bidirectional"))
    )
    (net (code "83") (name "/PIN49") (class "Default")
      (node (ref "RN1") (pin "2") (pinfunction "1_2") (pintype "passive"))
      (node (ref "U1") (pin "96") (pinfunction "PC14_96") (pintype "bidirectional"))
    )
    (net (code "84") (name "/PIN50") (class "Default")
      (node (ref "RN1") (pin "3") (pinfunction "1_3") (pintype "passive"))
      (node (ref "U1") (pin "95") (pinfunction "PC13_95") (pintype "bidirectional"))
    )
    (net (code "85") (name "/PIN51") (class "Default")
      (node (ref "RN1") (pin "4") (pinfunction "1_4") (pintype "passive"))
      (node (ref "U1") (pin "94") (pinfunction "PC12_94") (pintype "bidirectional"))
    )
    (net (code "86") (name "/PWM2") (class "Default")
      (node (ref "U1") (pin "144") (pinfunction "PB25_144") (pintype "bidirectional"))
    )
    (net (code "87") (name "/PWM3") (class "Default")
      (node (ref "U1") (pin "139") (pinfunction "PC28_139") (pintype "bidirectional"))
    )
    (net (code "88") (name "/PWM5") (class "Default")
      (node (ref "U1") (pin "136") (pinfunction "PC25_136") (pintype "bidirectional"))
    )
    (net (code "89") (name "/PWM6") (class "Default")
      (node (ref "U1") (pin "135") (pinfunction "PC24_135") (pintype "bidirectional"))
    )
    (net (code "90") (name "/PWM7") (class "Default")
      (node (ref "U1") (pin "134") (pinfunction "PC23_134") (pintype "bidirectional"))
    )
    (net (code "91") (name "/PWM8") (class "Default")
      (node (ref "U1") (pin "133") (pinfunction "PC22_133") (pintype "bidirectional"))
    )
    (net (code "92") (name "/PWM9") (class "Default")
      (node (ref "U1") (pin "132") (pinfunction "PC21_132") (pintype "bidirectional"))
    )
    (net (code "93") (name "/PWM11") (class "Default")
      (node (ref "U1") (pin "20") (pinfunction "PD7_20") (pintype "bidirectional"))
    )
    (net (code "94") (name "/PWM12") (class "Default")
      (node (ref "U1") (pin "21") (pinfunction "PD8_21") (pintype "bidirectional"))
    )
    (net (code "95") (name "/PWM13") (class "Default")
      (node (ref "U1") (pin "68") (pinfunction "PB27_68") (pintype "bidirectional"))
    )
    (net (code "96") (name "/RXD0") (class "Default")
      (node (ref "SERIAL0") (pin "1") (pinfunction "1_1") (pintype "passive"))
      (node (ref "U1") (pin "18") (pinfunction "PD5_18") (pintype "bidirectional"))
    )
    (net (code "97") (name "/RXD1") (class "Default")
      (node (ref "SERIAL1") (pin "1") (pinfunction "1_1") (pintype "passive"))
      (node (ref "U1") (pin "5") (pinfunction "PA12_5") (pintype "bidirectional"))
    )
    (net (code "98") (name "/RXL") (class "Default")
      (node (ref "U1") (pin "103") (pinfunction "PC30_103") (pintype "bidirectional"))
    )
    (net (code "99") (name "/RX_ARQ") (class "Default")
      (node (ref "ARQ_TERMINAL") (pin "2") (pinfunction "2_2") (pintype "passive"))
      (node (ref "MAX3232") (pin "14") (pinfunction "DOUT1_14") (pintype "output"))
    )
    (net (code "100") (name "/RX_DUE") (class "Default")
      (node (ref "ARQ_TERMINAL") (pin "6") (pinfunction "6_6") (pintype "passive"))
      (node (ref "R1") (pin "2") (pinfunction "2_2") (pintype "passive"))
      (node (ref "R9") (pin "2") (pinfunction "2_2") (pintype "passive"))
      (node (ref "U1") (pin "3") (pinfunction "PA10_3") (pintype "bidirectional"))
    )
    (net (code "101") (name "/RX_DUE1") (class "Default")
      (node (ref "MAX3232") (pin "12") (pinfunction "ROUT1_12") (pintype "output"))
      (node (ref "R1") (pin "1") (pinfunction "1_1") (pintype "passive"))
    )
    (net (code "102") (name "/RX_PROG") (class "Default")
      (node (ref "PROGRAMMER") (pin "3") (pinfunction "3_3") (pintype "passive"))
      (node (ref "R17") (pin "1") (pinfunction "1_1") (pintype "passive"))
      (node (ref "T8") (pin "3") (pinfunction "D_3") (pintype "passive"))
    )
    (net (code "103") (name "/RX_SAM") (class "Default")
      (node (ref "BT") (pin "4") (pinfunction "4_4") (pintype "passive"))
      (node (ref "R8") (pin "1") (pinfunction "1_1") (pintype "passive"))
      (node (ref "TP4") (pin "P$1") (pinfunction "1_P$1") (pintype "bidirectional"))
      (node (ref "U1") (pin "27") (pinfunction "PA8_27") (pintype "bidirectional"))
    )
    (net (code "104") (name "/SCL0-3") (class "Default")
      (node (ref "R3") (pin "1") (pinfunction "1_1") (pintype "passive"))
      (node (ref "U1") (pin "87") (pinfunction "PB13_87") (pintype "bidirectional"))
      (node (ref "U4") (pin "5") (pinfunction "SCL_5") (pintype "bidirectional"))
    )
    (net (code "105") (name "/SCL1") (class "Default")
      (node (ref "RTC") (pin "3") (pinfunction "3_3") (pintype "passive"))
      (node (ref "U1") (pin "70") (pinfunction "PA18_70") (pintype "bidirectional"))
    )
    (net (code "106") (name "/SDA0-3") (class "Default")
      (node (ref "R6") (pin "2") (pinfunction "2_2") (pintype "passive"))
      (node (ref "U1") (pin "86") (pinfunction "PB12_86") (pintype "bidirectional"))
      (node (ref "U4") (pin "6") (pinfunction "SDA_6") (pintype "bidirectional"))
    )
    (net (code "107") (name "/SDA1") (class "Default")
      (node (ref "RTC") (pin "2") (pinfunction "2_2") (pintype "passive"))
      (node (ref "U1") (pin "9") (pinfunction "PA17_9") (pintype "bidirectional"))
    )
    (net (code "108") (name "/SPCK") (class "Default")
      (node (ref "RN2") (pin "7") (pinfunction "2_7") (pintype "passive"))
      (node (ref "U$9") (pin "5") (pinfunction "SCK_5") (pintype "bidirectional"))
      (node (ref "U1") (pin "110") (pinfunction "PA27_110") (pintype "bidirectional"))
    )
    (net (code "109") (name "/SS3") (class "Default")
      (node (ref "RN2") (pin "5") (pinfunction "2_5") (pintype "passive"))
      (node (ref "U$9") (pin "2") (pinfunction "CS_2") (pintype "bidirectional"))
      (node (ref "U1") (pin "142") (pinfunction "PB23_142") (pintype "bidirectional"))
    )
    (net (code "110") (name "/SW") (class "Default")
      (node (ref "C42") (pin "2") (pinfunction "2_2") (pintype "passive"))
      (node (ref "D4") (pin "P$1") (pinfunction "K_P$1") (pintype "bidirectional"))
      (node (ref "IC2") (pin "6") (pinfunction "SW_6") (pintype "output"))
      (node (ref "L4") (pin "P$1") (pinfunction "1_P$1") (pintype "passive"))
    )
    (net (code "111") (name "/TXD0") (class "Default")
      (node (ref "SERIAL0") (pin "2") (pinfunction "2_2") (pintype "passive"))
      (node (ref "U1") (pin "17") (pinfunction "PD4_17") (pintype "bidirectional"))
    )
    (net (code "112") (name "/TXD1") (class "Default")
      (node (ref "SERIAL1") (pin "2") (pinfunction "2_2") (pintype "passive"))
      (node (ref "U1") (pin "6") (pinfunction "PA13_6") (pintype "bidirectional"))
    )
    (net (code "113") (name "/TXL") (class "Default")
      (node (ref "U1") (pin "107") (pinfunction "PA21_107") (pintype "bidirectional"))
    )
    (net (code "114") (name "/TX_ARQ") (class "Default")
      (node (ref "ARQ_TERMINAL") (pin "1") (pinfunction "1_1") (pintype "passive"))
      (node (ref "MAX3232") (pin "13") (pinfunction "RIN1_13") (pintype "input"))
    )
    (net (code "115") (name "/TX_DUE") (class "Default")
      (node (ref "ARQ_TERMINAL") (pin "5") (pinfunction "5_5") (pintype "passive"))
      (node (ref "R13") (pin "2") (pinfunction "2_2") (pintype "passive"))
      (node (ref "R2") (pin "2") (pinfunction "2_2") (pintype "passive"))
      (node (ref "U1") (pin "4") (pinfunction "PA11_4") (pintype "bidirectional"))
    )
    (net (code "116") (name "/TX_DUE1") (class "Default")
      (node (ref "MAX3232") (pin "11") (pinfunction "DIN1_11") (pintype "input"))
      (node (ref "R2") (pin "1") (pinfunction "1_1") (pintype "passive"))
    )
    (net (code "117") (name "/TX_PROG") (class "Default")
      (node (ref "PROGRAMMER") (pin "2") (pinfunction "2_2") (pintype "passive"))
      (node (ref "R16") (pin "1") (pinfunction "1_1") (pintype "passive"))
      (node (ref "T7") (pin "3") (pinfunction "D_3") (pintype "passive"))
    )
    (net (code "118") (name "/TX_SAM") (class "Default")
      (node (ref "BT") (pin "5") (pinfunction "5_5") (pintype "passive"))
      (node (ref "T7") (pin "2") (pinfunction "S_2") (pintype "passive"))
      (node (ref "TP3") (pin "P$1") (pinfunction "1_P$1") (pintype "bidirectional"))
      (node (ref "U1") (pin "2") (pinfunction "PA9_2") (pintype "bidirectional"))
    )
    (net (code "119") (name "/UOTGID") (class "Default")
      (node (ref "U1") (pin "129") (pinfunction "PB11_129") (pintype "bidirectional"))
    )
    (net (code "120") (name "/UOTGVBOF") (class "Default")
      (node (ref "U1") (pin "128") (pinfunction "PB10_128") (pintype "bidirectional"))
    )
    (net (code "121") (name "/USBVCC") (class "Default")
      (node (ref "PROGRAMMER") (pin "4") (pinfunction "4_4") (pintype "passive"))
      (node (ref "T1") (pin "1") (pinfunction "D_1") (pintype "passive"))
    )
    (net (code "122") (name "/VBG") (class "Default")
      (node (ref "C25") (pin "1") (pinfunction "1_1") (pintype "passive"))
      (node (ref "R7") (pin "2") (pinfunction "2_2") (pintype "passive"))
      (node (ref "U1") (pin "40") (pinfunction "VBG_40") (pintype "passive"))
    )
    (net (code "123") (name "/VDDANA") (class "Default")
      (node (ref "C10") (pin "2") (pinfunction "2_2") (pintype "passive"))
      (node (ref "C3") (pin "+") (pinfunction "+_+") (pintype "passive"))
      (node (ref "L1") (pin "2") (pinfunction "2_2") (pintype "passive"))
      (node (ref "U1") (pin "73") (pinfunction "VDDANA_73") (pintype "power_in"))
    )
    (net (code "124") (name "/VDDBU") (class "Default")
      (node (ref "U1") (pin "52") (pinfunction "VDDBU_52") (pintype "power_in"))
    )
    (net (code "125") (name "/VDDOUT") (class "Default")
      (node (ref "C11") (pin "+") (pinfunction "+_+") (pintype "passive"))
      (node (ref "C12") (pin "2") (pinfunction "2_2") (pintype "passive"))
      (node (ref "C13") (pin "2") (pinfunction "2_2") (pintype "passive"))
      (node (ref "C14") (pin "2") (pinfunction "2_2") (pintype "passive"))
      (node (ref "C15") (pin "2") (pinfunction "2_2") (pintype "passive"))
      (node (ref "C16") (pin "2") (pinfunction "2_2") (pintype "passive"))
      (node (ref "C17") (pin "2") (pinfunction "2_2") (pintype "passive"))
      (node (ref "L5") (pin "1") (pinfunction "1_1") (pintype "passive"))
      (node (ref "U1") (pin "10") (pinfunction "VDDCORE1_10") (pintype "input"))
      (node (ref "U1") (pin "104") (pinfunction "VDDCORE4_104") (pintype "input"))
      (node (ref "U1") (pin "124") (pinfunction "VDDCORE5_124") (pintype "input"))
      (node (ref "U1") (pin "45") (pinfunction "VDDCORE2_45") (pintype "input"))
      (node (ref "U1") (pin "56") (pinfunction "VDDOUT_56") (pintype "output"))
      (node (ref "U1") (pin "61") (pinfunction "VDDCORE3_61") (pintype "input"))
    )
    (net (code "126") (name "/VDDOUTMI") (class "Default")
      (node (ref "C2") (pin "+") (pinfunction "+_+") (pintype "passive"))
      (node (ref "C9") (pin "2") (pinfunction "2_2") (pintype "passive"))
      (node (ref "L2") (pin "2") (pinfunction "2_2") (pintype "passive"))
      (node (ref "U1") (pin "41") (pinfunction "VDDUTMI_41") (pintype "input"))
    )
    (net (code "127") (name "/VDDPLL") (class "Default")
      (node (ref "C32") (pin "2") (pinfunction "2_2") (pintype "passive"))
      (node (ref "C33") (pin "+") (pinfunction "+_+") (pintype "passive"))
      (node (ref "L5") (pin "2") (pinfunction "2_2") (pintype "passive"))
      (node (ref "U1") (pin "34") (pinfunction "VDDPLL_34") (pintype "input"))
    )
    (net (code "128") (name "/VIN") (class "Default")
      (node (ref "F1") (pin "2") (pinfunction "2_2") (pintype "bidirectional"))
      (node (ref "JP2") (pin "2") (pinfunction "2_2") (pintype "passive"))
      (node (ref "U2") (pin "3") (pinfunction "OUT_3") (pintype "bidirectional"))
    )
    (net (code "129") (name "/VIN_DUE") (class "Default")
      (node (ref "C41") (pin "+") (pinfunction "+_+") (pintype "passive"))
      (node (ref "D1") (pin "C") (pinfunction "C_C") (pintype "passive"))
      (node (ref "F1") (pin "1") (pinfunction "1_1") (pintype "bidirectional"))
      (node (ref "IC2") (pin "5") (pinfunction "VIN_5") (pintype "input"))
      (node (ref "PC1") (pin "+") (pinfunction "+_+") (pintype "passive"))
      (node (ref "R10") (pin "1") (pinfunction "1_1") (pintype "passive"))
      (node (ref "RN4") (pin "6") (pinfunction "2_6") (pintype "passive"))
    )
    (net (code "130") (name "/XIN") (class "Default")
      (node (ref "C22") (pin "1") (pinfunction "1_1") (pintype "passive"))
      (node (ref "U1") (pin "36") (pinfunction "XIN_36") (pintype "input"))
      (node (ref "Y1") (pin "1") (pinfunction "C1_1") (pintype "passive"))
    )
    (net (code "131") (name "/XIN32") (class "Default")
      (node (ref "C24") (pin "1") (pinfunction "1_1") (pintype "passive"))
      (node (ref "U1") (pin "48") (pinfunction "XIN32_48") (pintype "output"))
      (node (ref "Y2") (pin "P$2") (pinfunction "2_P$2") (pintype "bidirectional"))
    )
    (net (code "132") (name "/XOUT") (class "Default")
      (node (ref "C21") (pin "1") (pinfunction "1_1") (pintype "passive"))
      (node (ref "U1") (pin "35") (pinfunction "XOUT_35") (pintype "output"))
      (node (ref "Y1") (pin "3") (pinfunction "C2_3") (pintype "passive"))
    )
    (net (code "133") (name "/XOUT32") (class "Default")
      (node (ref "C23") (pin "1") (pinfunction "1_1") (pintype "passive"))
      (node (ref "U1") (pin "49") (pinfunction "XOUT32_49") (pintype "output"))
      (node (ref "Y2") (pin "P$1") (pinfunction "1_P$1") (pintype "bidirectional"))
    )
    (net (code "134") (name "GND") (class "Default")
      (node (ref "ARQ_TERMINAL") (pin "4") (pinfunction "4_4") (pintype "passive"))
      (node (ref "BT") (pin "3") (pinfunction "3_3") (pintype "passive"))
      (node (ref "C1") (pin "-") (pinfunction "-_-") (pintype "passive"))
      (node (ref "C1-C") (pin "2") (pinfunction "2_2") (pintype "passive"))
      (node (ref "C10") (pin "1") (pinfunction "1_1") (pintype "passive"))
      (node (ref "C11") (pin "-") (pinfunction "-_-") (pintype "passive"))
      (node (ref "C12") (pin "1") (pinfunction "1_1") (pintype "passive"))
      (node (ref "C13") (pin "1") (pinfunction "1_1") (pintype "passive"))
      (node (ref "C14") (pin "1") (pinfunction "1_1") (pintype "passive"))
      (node (ref "C15") (pin "1") (pinfunction "1_1") (pintype "passive"))
      (node (ref "C16") (pin "1") (pinfunction "1_1") (pintype "passive"))
      (node (ref "C17") (pin "1") (pinfunction "1_1") (pintype "passive"))
      (node (ref "C18") (pin "1") (pinfunction "1_1") (pintype "passive"))
      (node (ref "C19") (pin "2") (pinfunction "2_2") (pintype "passive"))
      (node (ref "C2") (pin "-") (pinfunction "-_-") (pintype "passive"))
      (node (ref "C20") (pin "2") (pinfunction "P$2_2") (pintype "passive"))
      (node (ref "C21") (pin "2") (pinfunction "2_2") (pintype "passive"))
      (node (ref "C22") (pin "2") (pinfunction "2_2") (pintype "passive"))
      (node (ref "C23") (pin "2") (pinfunction "2_2") (pintype "passive"))
      (node (ref "C24") (pin "2") (pinfunction "2_2") (pintype "passive"))
      (node (ref "C25") (pin "2") (pinfunction "2_2") (pintype "passive"))
      (node (ref "C29") (pin "-") (pinfunction "-_-") (pintype "passive"))
      (node (ref "C3") (pin "-") (pinfunction "-_-") (pintype "passive"))
      (node (ref "C30") (pin "1") (pinfunction "1_1") (pintype "passive"))
      (node (ref "C31") (pin "1") (pinfunction "1_1") (pintype "passive"))
      (node (ref "C32") (pin "1") (pinfunction "1_1") (pintype "passive"))
      (node (ref "C33") (pin "-") (pinfunction "-_-") (pintype "passive"))
      (node (ref "C38") (pin "1") (pinfunction "1_1") (pintype "passive"))
      (node (ref "C39") (pin "2") (pinfunction "2_2") (pintype "passive"))
      (node (ref "C4") (pin "1") (pinfunction "1_1") (pintype "passive"))
      (node (ref "C41") (pin "-") (pinfunction "-_-") (pintype "passive"))
      (node (ref "C5") (pin "1") (pinfunction "1_1") (pintype "passive"))
      (node (ref "C6") (pin "1") (pinfunction "1_1") (pintype "passive"))
      (node (ref "C7") (pin "1") (pinfunction "1_1") (pintype "passive"))
      (node (ref "C8") (pin "1") (pinfunction "1_1") (pintype "passive"))
      (node (ref "C9") (pin "1") (pinfunction "1_1") (pintype "passive"))
      (node (ref "D1") (pin "A") (pinfunction "A_A") (pintype "passive"))
      (node (ref "D4") (pin "P$2") (pinfunction "A_P$2") (pintype "bidirectional"))
      (node (ref "D5") (pin "A") (pinfunction "A_A") (pintype "passive"))
      (node (ref "IC1") (pin "4") (pinfunction "V-_4") (pintype "power_in"))
      (node (ref "IC2") (pin "2") (pinfunction "GND_2") (pintype "power_in"))
      (node (ref "IC4") (pin "1") (pinfunction "GND/ADJ_1") (pintype "input"))
      (node (ref "IO1") (pin "1") (pinfunction "1_1") (pintype "passive"))
      (node (ref "LED1") (pin "C") (pinfunction "C_C") (pintype "passive"))
      (node (ref "LED2") (pin "C") (pinfunction "C_C") (pintype "passive"))
      (node (ref "LED3") (pin "C") (pinfunction "C_C") (pintype "passive"))
      (node (ref "LED4") (pin "C") (pinfunction "C_C") (pintype "passive"))
      (node (ref "MAX3232") (pin "15") (pinfunction "GND_15") (pintype "passive"))
      (node (ref "PC1") (pin "-") (pinfunction "-_-") (pintype "passive"))
      (node (ref "PC2") (pin "-") (pinfunction "-_-") (pintype "passive"))
      (node (ref "PROGRAMMER") (pin "6") (pinfunction "6_6") (pintype "passive"))
      (node (ref "Q4") (pin "1") (pinfunction "GND_1") (pintype "passive"))
      (node (ref "R11") (pin "2") (pinfunction "2_2") (pintype "passive"))
      (node (ref "R14") (pin "1") (pinfunction "1_1") (pintype "passive"))
      (node (ref "R15") (pin "1") (pinfunction "1_1") (pintype "passive"))
      (node (ref "R22") (pin "1") (pinfunction "1_1") (pintype "passive"))
      (node (ref "R23") (pin "1") (pinfunction "1_1") (pintype "passive"))
      (node (ref "R7") (pin "1") (pinfunction "1_1") (pintype "passive"))
      (node (ref "RG") (pin "3") (pinfunction "3_3") (pintype "passive"))
      (node (ref "RN4") (pin "2") (pinfunction "1_2") (pintype "passive"))
      (node (ref "RN4") (pin "5") (pinfunction "2_5") (pintype "passive"))
      (node (ref "RN4") (pin "7") (pinfunction "2_7") (pintype "passive"))
      (node (ref "RTC") (pin "5") (pinfunction "5_5") (pintype "passive"))
      (node (ref "SERIAL0") (pin "3") (pinfunction "3_3") (pintype "passive"))
      (node (ref "SERIAL1") (pin "3") (pinfunction "3_3") (pintype "passive"))
      (node (ref "U$9") (pin "6") (pinfunction "GND_6") (pintype "bidirectional"))
      (node (ref "U$9") (pin "SHIELD@1") (pinfunction "SHIELD_SHIELD@1") (pintype "bidirectional"))
      (node (ref "U$9") (pin "SHIELD@2") (pinfunction "SHIELD_SHIELD@2") (pintype "bidirectional"))
      (node (ref "U$9") (pin "SHIELD@3") (pinfunction "SHIELD_SHIELD@3") (pintype "bidirectional"))
      (node (ref "U$9") (pin "SHIELD@4") (pinfunction "SHIELD_SHIELD@4") (pintype "bidirectional"))
      (node (ref "U$9") (pin "SHIELD@5") (pinfunction "SHIELD_SHIELD@5") (pintype "bidirectional"))
      (node (ref "U1") (pin "106") (pinfunction "GND3_106") (pintype "power_in"))
      (node (ref "U1") (pin "12") (pinfunction "GND1_12") (pintype "power_in"))
      (node (ref "U1") (pin "126") (pinfunction "GND4_126") (pintype "power_in"))
      (node (ref "U1") (pin "33") (pinfunction "GNDPLL_33") (pintype "power_in"))
      (node (ref "U1") (pin "44") (pinfunction "GNDUTMI_44") (pintype "power_in"))
      (node (ref "U1") (pin "46") (pinfunction "JTAGSEL_46") (pintype "input"))
      (node (ref "U1") (pin "51") (pinfunction "TST_51") (pintype "input"))
      (node (ref "U1") (pin "58") (pinfunction "GND2_58") (pintype "power_in"))
      (node (ref "U1") (pin "74") (pinfunction "GNDANA_74") (pintype "power_in"))
      (node (ref "U1") (pin "75") (pinfunction "ADVREF_75") (pintype "power_in"))
      (node (ref "U2") (pin "1") (pinfunction "GND_1") (pintype "bidirectional"))
      (node (ref "U2-C") (pin "2") (pinfunction "GND_2") (pintype "bidirectional"))
      (node (ref "U2-C1") (pin "3") (pinfunction "3_3") (pintype "output"))
      (node (ref "U4") (pin "3") (pinfunction "GND_3") (pintype "bidirectional"))
      (node (ref "X11") (pin "1") (pinfunction "KL_1") (pintype "passive"))
      (node (ref "X2") (pin "2") (pinfunction "KL_2") (pintype "passive"))
      (node (ref "X3") (pin "1") (pinfunction "KL_1") (pintype "passive"))
      (node (ref "X4") (pin "1") (pinfunction "KL_1") (pintype "passive"))
      (node (ref "X5") (pin "2") (pinfunction "KL_2") (pintype "passive"))
      (node (ref "X6") (pin "2") (pinfunction "KL_2") (pintype "passive"))
      (node (ref "X7") (pin "1") (pinfunction "KL_1") (pintype "passive"))
      (node (ref "Y1") (pin "2") (pinfunction "GND_2") (pintype "passive"))
      (node (ref "Y1") (pin "4") (pinfunction "GND_4") (pintype "passive"))
    )
    (net (code "135") (name "Net-(C1-C-Pad1)") (class "Default")
      (node (ref "C1-C") (pin "1") (pinfunction "1_1") (pintype "passive"))
      (node (ref "R1-C5") (pin "1") (pinfunction "1_1") (pintype "passive"))
      (node (ref "R2-C") (pin "2") (pinfunction "2_2") (pintype "passive"))
    )
    (net (code "136") (name "Net-(MAX3232-C1+)") (class "Default")
      (node (ref "C35") (pin "1") (pinfunction "1_1") (pintype "passive"))
      (node (ref "MAX3232") (pin "1") (pinfunction "C1+_1") (pintype "input"))
    )
    (net (code "137") (name "Net-(MAX3232-C1-)") (class "Default")
      (node (ref "C35") (pin "2") (pinfunction "2_2") (pintype "passive"))
      (node (ref "MAX3232") (pin "3") (pinfunction "C1-_3") (pintype "input"))
    )
    (net (code "138") (name "Net-(MAX3232-C2+)") (class "Default")
      (node (ref "C36") (pin "1") (pinfunction "1_1") (pintype "passive"))
      (node (ref "MAX3232") (pin "4") (pinfunction "C2+_4") (pintype "input"))
    )
    (net (code "139") (name "Net-(MAX3232-C2-)") (class "Default")
      (node (ref "C36") (pin "2") (pinfunction "2_2") (pintype "passive"))
      (node (ref "MAX3232") (pin "5") (pinfunction "C2-_5") (pintype "input"))
    )
    (net (code "140") (name "Net-(MAX3232-V+)") (class "Default")
      (node (ref "C37") (pin "2") (pinfunction "2_2") (pintype "passive"))
      (node (ref "MAX3232") (pin "2") (pinfunction "V+_2") (pintype "power_in"))
    )
    (net (code "141") (name "Net-(MAX3232-V-)") (class "Default")
      (node (ref "C38") (pin "2") (pinfunction "2_2") (pintype "passive"))
      (node (ref "MAX3232") (pin "6") (pinfunction "V-_6") (pintype "power_in"))
    )
    (net (code "142") (name "Net-(Q1-B)") (class "Default")
      (node (ref "Q1") (pin "1") (pinfunction "B_1") (pintype "passive"))
      (node (ref "R9") (pin "1") (pinfunction "1_1") (pintype "passive"))
    )
    (net (code "143") (name "Net-(Q1-C)") (class "Default")
      (node (ref "Q1") (pin "3") (pinfunction "C_3") (pintype "passive"))
      (node (ref "RX_DUE") (pin "A") (pinfunction "A_A") (pintype "passive"))
    )
    (net (code "144") (name "Net-(Q2-B)") (class "Default")
      (node (ref "Q2") (pin "1") (pinfunction "B_1") (pintype "passive"))
      (node (ref "R13") (pin "1") (pinfunction "1_1") (pintype "passive"))
    )
    (net (code "145") (name "Net-(Q2-C)") (class "Default")
      (node (ref "Q2") (pin "3") (pinfunction "C_3") (pintype "passive"))
      (node (ref "TX_DUE") (pin "A") (pinfunction "A_A") (pintype "passive"))
    )
    (net (code "146") (name "Net-(Q4-IN)") (class "Default")
      (node (ref "Q4") (pin "2") (pinfunction "IN_2") (pintype "passive"))
      (node (ref "R5") (pin "2") (pinfunction "2_2") (pintype "passive"))
    )
    (net (code "147") (name "Net-(Q4-OUT)") (class "Default")
      (node (ref "FUSE1") (pin "1") (pinfunction "1_1") (pintype "passive"))
      (node (ref "Q4") (pin "5") (pinfunction "OUT_5") (pintype "passive"))
    )
    (net (code "148") (name "Net-(R14-Pad2)") (class "Default")
      (node (ref "R14") (pin "2") (pinfunction "2_2") (pintype "passive"))
      (node (ref "TX_DUE") (pin "C") (pinfunction "C_C") (pintype "passive"))
    )
    (net (code "149") (name "Net-(R15-Pad2)") (class "Default")
      (node (ref "R15") (pin "2") (pinfunction "2_2") (pintype "passive"))
      (node (ref "RX_DUE") (pin "C") (pinfunction "C_C") (pintype "passive"))
    )
    (net (code "150") (name "Net-(RN1A-2)") (class "Default")
      (node (ref "LED1") (pin "A") (pinfunction "A_A") (pintype "passive"))
      (node (ref "RN1") (pin "8") (pinfunction "2_8") (pintype "passive"))
    )
    (net (code "151") (name "Net-(RN1B-2)") (class "Default")
      (node (ref "LED2") (pin "A") (pinfunction "A_A") (pintype "passive"))
      (node (ref "RN1") (pin "7") (pinfunction "2_7") (pintype "passive"))
    )
    (net (code "152") (name "Net-(RN1C-2)") (class "Default")
      (node (ref "LED3") (pin "A") (pinfunction "A_A") (pintype "passive"))
      (node (ref "RN1") (pin "6") (pinfunction "2_6") (pintype "passive"))
    )
    (net (code "153") (name "Net-(RN1D-2)") (class "Default")
      (node (ref "LED4") (pin "A") (pinfunction "A_A") (pintype "passive"))
      (node (ref "RN1") (pin "5") (pinfunction "2_5") (pintype "passive"))
    )
    (net (code "154") (name "Net-(T8-S)") (class "Default")
      (node (ref "R8") (pin "2") (pinfunction "2_2") (pintype "passive"))
      (node (ref "T8") (pin "2") (pinfunction "S_2") (pintype "passive"))
    )
    (net (code "155") (name "Net-(U1-FWUP)") (class "Default")
      (node (ref "R4") (pin "1") (pinfunction "1_1") (pintype "passive"))
      (node (ref "U1") (pin "53") (pinfunction "FWUP_53") (pintype "input"))
    )
    (net (code "156") (name "Net-(U2-IN)") (class "Default")
      (node (ref "R18") (pin "2") (pinfunction "2_2") (pintype "passive"))
      (node (ref "U2") (pin "2") (pinfunction "IN_2") (pintype "bidirectional"))
    )
    (net (code "157") (name "Net-(U4-A0)") (class "Default")
      (node (ref "R22") (pin "2") (pinfunction "2_2") (pintype "passive"))
      (node (ref "SJ4") (pin "2") (pinfunction "2_2") (pintype "passive"))
      (node (ref "U4") (pin "7") (pinfunction "A0_7") (pintype "bidirectional"))
    )
    (net (code "158") (name "Net-(U4-A1)") (class "Default")
      (node (ref "R23") (pin "2") (pinfunction "2_2") (pintype "passive"))
      (node (ref "SJ3") (pin "2") (pinfunction "2_2") (pintype "passive"))
      (node (ref "U4") (pin "8") (pinfunction "A1_8") (pintype "bidirectional"))
    )
    (net (code "159") (name "XUSB") (class "Default")
      (node (ref "U1") (pin "39") (pinfunction "VBUS_39") (pintype "power_in"))
    )
    (net (code "160") (name "unconnected-(BT-Pad1)") (class "Default")
      (node (ref "BT") (pin "1") (pinfunction "1_1") (pintype "passive"))
    )
    (net (code "161") (name "unconnected-(BT-Pad6)") (class "Default")
      (node (ref "BT") (pin "6") (pinfunction "6_6") (pintype "passive"))
    )
    (net (code "162") (name "unconnected-(MAX3232-DIN2-Pad10)") (class "Default")
      (node (ref "MAX3232") (pin "10") (pinfunction "DIN2_10") (pintype "input"))
    )
    (net (code "163") (name "unconnected-(MAX3232-DOUT2-Pad7)") (class "Default")
      (node (ref "MAX3232") (pin "7") (pinfunction "DOUT2_7") (pintype "output"))
    )
    (net (code "164") (name "unconnected-(MAX3232-RIN2-Pad8)") (class "Default")
      (node (ref "MAX3232") (pin "8") (pinfunction "RIN2_8") (pintype "input"))
    )
    (net (code "165") (name "unconnected-(MAX3232-ROUT2-Pad9)") (class "Default")
      (node (ref "MAX3232") (pin "9") (pinfunction "ROUT2_9") (pintype "output"))
    )
    (net (code "166") (name "unconnected-(RTC-Pad4)") (class "Default")
      (node (ref "RTC") (pin "4") (pinfunction "4_4") (pintype "passive"))
    )
    (net (code "167") (name "unconnected-(U$9-NC-Pad1)") (class "Default")
      (node (ref "U$9") (pin "1") (pinfunction "NC_1") (pintype "bidirectional"))
    )
    (net (code "168") (name "unconnected-(U$9-PadCD1)") (class "Default")
      (node (ref "U$9") (pin "CD1") (pinfunction "CD1_CD1") (pintype "bidirectional"))
    )
    (net (code "169") (name "unconnected-(U$9-PadCD2)") (class "Default")
      (node (ref "U$9") (pin "CD2") (pinfunction "CD2_CD2") (pintype "bidirectional"))
    )
    (net (code "170") (name "unconnected-(U$9-RSV-Pad8)") (class "Default")
      (node (ref "U$9") (pin "8") (pinfunction "RSV_8") (pintype "bidirectional"))
    )
    (net (code "171") (name "unconnected-(U1-DFSDM-Pad43)") (class "Default")
      (node (ref "U1") (pin "43") (pinfunction "DFSDM_43") (pintype "input"))
    )
    (net (code "172") (name "unconnected-(U1-DFSDP-Pad42)") (class "Default")
      (node (ref "U1") (pin "42") (pinfunction "DFSDP_42") (pintype "input"))
    )
    (net (code "173") (name "unconnected-(U1-DHSDM-Pad38)") (class "Default")
      (node (ref "U1") (pin "38") (pinfunction "DHSDM_38") (pintype "bidirectional"))
    )
    (net (code "174") (name "unconnected-(U1-DHSDP-Pad37)") (class "Default")
      (node (ref "U1") (pin "37") (pinfunction "DHSDP_37") (pintype "bidirectional"))
    )
    (net (code "175") (name "unconnected-(U1-NRSTB-Pad47)") (class "Default")
      (node (ref "U1") (pin "47") (pinfunction "NRSTB_47") (pintype "input"))
    )
    (net (code "176") (name "unconnected-(U1-PA28-Pad111)") (class "Default")
      (node (ref "U1") (pin "111") (pinfunction "PA28_111") (pintype "bidirectional"))
    )
    (net (code "177") (name "unconnected-(U1-PA29-Pad112)") (class "Default")
      (node (ref "U1") (pin "112") (pinfunction "PA29_112") (pintype "bidirectional"))
    )
    (net (code "178") (name "unconnected-(U1-PB22-Pad141)") (class "Default")
      (node (ref "U1") (pin "141") (pinfunction "PB22_141") (pintype "bidirectional"))
    )
    (net (code "179") (name "unconnected-(U1-PB24-Pad143)") (class "Default")
      (node (ref "U1") (pin "143") (pinfunction "PB24_143") (pintype "bidirectional"))
    )
    (net (code "180") (name "unconnected-(U1-PC10-Pad117)") (class "Default")
      (node (ref "U1") (pin "117") (pinfunction "PC10_117") (pintype "bidirectional"))
    )
    (net (code "181") (name "unconnected-(U1-PC11-Pad93)") (class "Default")
      (node (ref "U1") (pin "93") (pinfunction "PC11_93") (pintype "bidirectional"))
    )
    (net (code "182") (name "unconnected-(U1-PC20-Pad131)") (class "Default")
      (node (ref "U1") (pin "131") (pinfunction "PC20_131") (pintype "bidirectional"))
    )
    (net (code "183") (name "unconnected-(U1-PC26-Pad137)") (class "Default")
      (node (ref "U1") (pin "137") (pinfunction "PC26_137") (pintype "bidirectional"))
    )
    (net (code "184") (name "unconnected-(U1-PC27-Pad138)") (class "Default")
      (node (ref "U1") (pin "138") (pinfunction "PC27_138") (pintype "bidirectional"))
    )
    (net (code "185") (name "unconnected-(U1-PC29-Pad102)") (class "Default")
      (node (ref "U1") (pin "102") (pinfunction "PC29_102") (pintype "bidirectional"))
    )
    (net (code "186") (name "unconnected-(U1-SHDN-Pad50)") (class "Default")
      (node (ref "U1") (pin "50") (pinfunction "SHDN_50") (pintype "output"))
    )
    (net (code "187") (name "unconnected-(U2-ST-Pad4)") (class "Default")
      (node (ref "U2") (pin "4") (pinfunction "ST_4") (pintype "bidirectional"))
    )
  )
)
